# LiPoBattery.net
KiCad netlist of a schematic drawn in Altium Designer
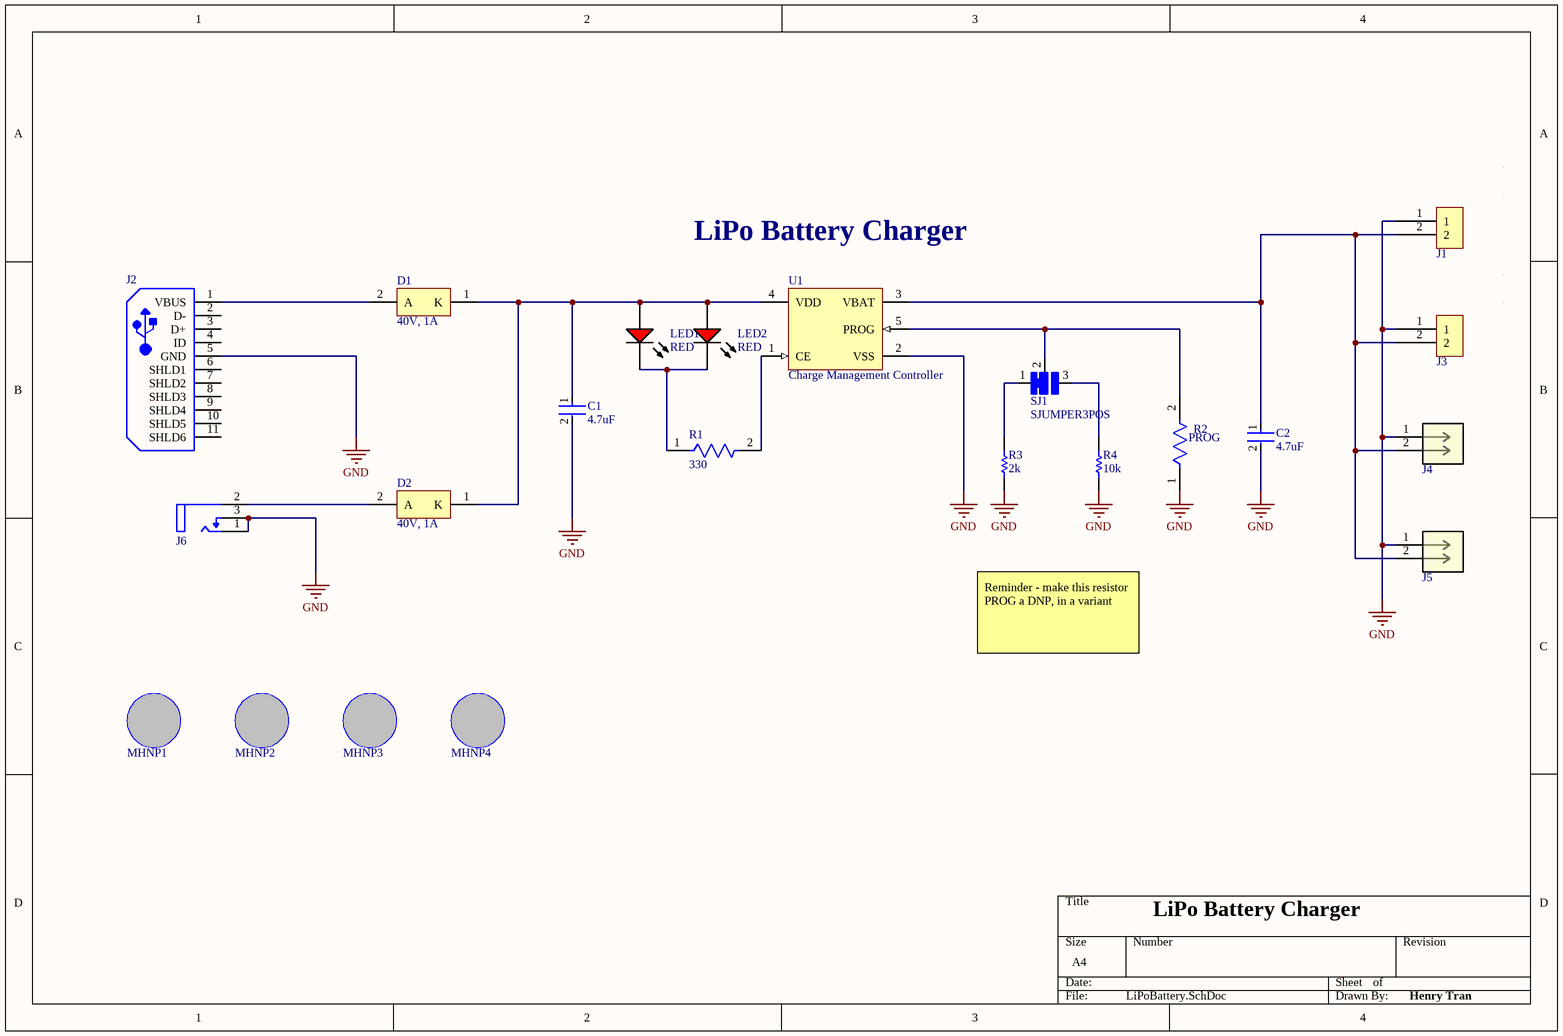
[diagram p0: LiPoBattery.SchDoc]

(export (version "E")
  (design (tool "Eeschema 10.0.6"))
  (components
    (comp (ref "C1")
      (value "4.7uF")
      (footprint "FP-CC0805-0_85-MFG")
      (description "CAP CER 4.7UF 6.3V X5R 0805")
      (fields (field (name "MANUFACTURER") "Yageo") (field (name "TOLERANCE") "0.1"))
      (libsource (lib "Altium Content Vault") (part "11868f565c42a9108669ba33697ecf6"))
    )
    (comp (ref "C2")
      (value "4.7uF")
      (footprint "FP-CC0805-0_85-MFG")
      (description "CAP CER 4.7UF 6.3V X5R 0805")
      (fields (field (name "MANUFACTURER") "Yageo") (field (name "TOLERANCE") "0.1"))
      (libsource (lib "Altium Content Vault") (part "11868f565c42a9108669ba33697ecf6"))
    )
    (comp (ref "D1")
      (value "40V, 1A")
      (footprint "ONSC-SMA-2-403D-02_V")
      (description "Schottky Power Rectifier, 2-Pin SMA, Pb-Free, Tape and Reel")
      (fields (field (name "PARTNUMBER") "MBRA140T3G") (field (name "MANUFACTURER") "On Semiconductor"))
      (libsource (lib "Altium Content Vault") (part "ONSC-D-K1A2-2_A"))
    )
    (comp (ref "D2")
      (value "40V, 1A")
      (footprint "ONSC-SMA-2-403D-02_V")
      (description "Schottky Power Rectifier, 2-Pin SMA, Pb-Free, Tape and Reel")
      (fields (field (name "PARTNUMBER") "MBRA140T3G") (field (name "MANUFACTURER") "On Semiconductor"))
      (libsource (lib "Altium Content Vault") (part "ONSC-D-K1A2-2_A"))
    )
    (comp (ref "J1")
      (value "CONN HEADER R/A 2POS 5.08MM")
      (footprint "1-179276-2")
      (description "Connector Header Through Hole, Right Angle 2 position 0.200\" (5.08mm)")
      (fields
        (field (name "MANUFACTURER") "TE Connectivity AMP Connectors")
        (field (name "MANUFACTURER PART NUMBER") "1-179276-2")
      )
      (libsource (lib "LiPoBattery") (part "1-179276-2"))
    )
    (comp (ref "J2")
      (value "105017-0001")
      (footprint "USB-MICRO-B_V")
      (fields (field (name "MANUFACTURER") "Molex"))
      (libsource (lib "Altium Content Vault") (part "USB-5-6SHLD"))
    )
    (comp (ref "J3")
      (value "CONN HEADER R/A 2POS 5.08MM")
      (footprint "1-179276-2")
      (description "Connector Header Through Hole, Right Angle 2 position 0.200\" (5.08mm)")
      (fields
        (field (name "MANUFACTURER") "TE Connectivity AMP Connectors")
        (field (name "MANUFACTURER PART NUMBER") "1-179276-2")
      )
      (libsource (lib "LiPoBattery") (part "1-179276-2"))
    )
    (comp (ref "J4")
      (value "2 POS VERT HEADER  0.100\"")
      (footprint "2Pins_AMP")
      (description "Connector Header Through Hole 2 position")
      (libsource (lib "LiPoBattery") (part "67997-402HLF"))
    )
    (comp (ref "J5")
      (value "2 POS VERT HEADER  0.100\"")
      (footprint "2Pins_AMP")
      (description "Connector Header Through Hole 2 position")
      (libsource (lib "LiPoBattery") (part "67997-402HLF"))
    )
    (comp (ref "J6")
      (value "CONN PWR JACK 2.1X5.5MM SOLDER")
      (footprint "FP-RASM722PTR13X-MFG")
      (libsource (lib "Altium Content Vault") (part "69023cd999ddc70d2a190894d9bbb58"))
    )
    (comp (ref "LED1")
      (value "RED")
      (footprint "VISH-TLMS1000_V")
      (description "Low Current LED, 40 mW, 1.8 V, -40 to 100 degC, 2-Pin SMD (0603), RoHS, Tape and Reel")
      (fields (field (name "MANUFACTURER") "Vishay"))
      (libsource (lib "Altium Content Vault") (part "LED-RED-AK-2"))
    )
    (comp (ref "LED2")
      (value "RED")
      (footprint "VISH-TLMS1000_V")
      (description "Low Current LED, 40 mW, 1.8 V, -40 to 100 degC, 2-Pin SMD (0603), RoHS, Tape and Reel")
      (fields (field (name "MANUFACTURER") "Vishay"))
      (libsource (lib "Altium Content Vault") (part "LED-RED-AK-2"))
    )
    (comp (ref "MHNP1")
      (value "Mounting Hole Non-Plated 3.2mm")
      (footprint "MTHNP3P2MM")
      (description "Mounting Hole Non-Plated 3.2mm drill hole")
      (libsource (lib "LiPoBattery") (part "MTHNP3P2MM"))
    )
    (comp (ref "MHNP2")
      (value "Mounting Hole Non-Plated 3.2mm")
      (footprint "MTHNP3P2MM")
      (description "Mounting Hole Non-Plated 3.2mm drill hole")
      (libsource (lib "LiPoBattery") (part "MTHNP3P2MM"))
    )
    (comp (ref "MHNP3")
      (value "Mounting Hole Non-Plated 3.2mm")
      (footprint "MTHNP3P2MM")
      (description "Mounting Hole Non-Plated 3.2mm drill hole")
      (libsource (lib "LiPoBattery") (part "MTHNP3P2MM"))
    )
    (comp (ref "MHNP4")
      (value "Mounting Hole Non-Plated 3.2mm")
      (footprint "MTHNP3P2MM")
      (description "Mounting Hole Non-Plated 3.2mm drill hole")
      (libsource (lib "LiPoBattery") (part "MTHNP3P2MM"))
    )
    (comp (ref "R1")
      (value "330")
      (footprint "FP-CRCW0805-e3-MFG")
      (description "RES Thick Film, 330Ω, 1%, 0.125W, 100ppm/°C, 0805")
      (fields (field (name "TOLERANCE") "1%"))
      (libsource (lib "Altium Content Vault") (part "1029c3af85768c4190bb7ad29bc67b5"))
    )
    (comp (ref "R2")
      (value "PROG")
      (footprint "FP-MRS25-MFG")
      (fields (field (name "TOLERANCE") "1%"))
      (libsource (lib "Altium Content Vault") (part "1029c3af85768c4190bb7ad29bc67b5"))
    )
    (comp (ref "R3")
      (value "2k")
      (footprint "RESC2013X70X40ML20T20")
      (fields (field (name "PART NUMBER") "ERJ-6GEYJ202V") (field (name "MANUFACTURER") "Panasonic"))
      (libsource (lib "Altium Content Vault") (part "RES"))
    )
    (comp (ref "R4")
      (value "10k")
      (footprint "RESC2013X70X40ML20T20")
      (fields (field (name "MANUFACTURER") "Panasonic") (field (name "PART NUMBER") "ERJ-6ENF1002V"))
      (libsource (lib "Altium Content Vault") (part "RES"))
    )
    (comp (ref "SJ1")
      (value "SJUMPER3POS")
      (footprint "SJUMPER3POS-Footprint-1")
      (description "Solder jumer 3 pads and pins")
      (libsource (lib "Altium 365 Cloud") (part "SJUMPER3POS-Symbol-1"))
    )
    (comp (ref "U1")
      (value "Charge Management Controller")
      (footprint "SOT-23-OT5_M")
      (libsource (lib "Altium Content Vault") (part "PM-BM-MCP7381X-SOT5"))
    )
  )
  (nets
    (net (code "1") (name "GND") (class "Default")
      (node (ref "C1") (pin "2") (pinfunction "2_2") (pintype "passive"))
      (node (ref "C2") (pin "2") (pinfunction "2_2") (pintype "passive"))
      (node (ref "J1") (pin "1") (pinfunction "1_1") (pintype "passive"))
      (node (ref "J2") (pin "5") (pinfunction "GND_5") (pintype "passive"))
      (node (ref "J3") (pin "1") (pinfunction "1_1") (pintype "passive"))
      (node (ref "J4") (pin "1") (pinfunction "1_1") (pintype "passive"))
      (node (ref "J5") (pin "1") (pinfunction "1_1") (pintype "passive"))
      (node (ref "J6") (pin "1") (pinfunction "TIP_TERMINAL(CENTER_PIN)_1") (pintype "passive"))
      (node (ref "J6") (pin "3") (pinfunction "SHUNT_TERMINAL_3") (pintype "passive"))
      (node (ref "R2") (pin "1") (pinfunction "1_1") (pintype "passive"))
      (node (ref "R3") (pin "1") (pinfunction "1_1") (pintype "passive"))
      (node (ref "R4") (pin "1") (pinfunction "1_1") (pintype "passive"))
      (node (ref "U1") (pin "2") (pinfunction "VSS_2") (pintype "power_in"))
    )
    (net (code "2") (name "Net-(D1-A)") (class "Default")
      (node (ref "D1") (pin "2") (pinfunction "A_2") (pintype "passive"))
      (node (ref "J2") (pin "1") (pinfunction "VBUS_1") (pintype "passive"))
    )
    (net (code "3") (name "Net-(D1-K)") (class "Default")
      (node (ref "C1") (pin "1") (pinfunction "1_1") (pintype "passive"))
      (node (ref "D1") (pin "1") (pinfunction "K_1") (pintype "passive"))
      (node (ref "D2") (pin "1") (pinfunction "K_1") (pintype "passive"))
      (node (ref "LED1") (pin "1") (pinfunction "A_1") (pintype "passive"))
      (node (ref "LED2") (pin "1") (pinfunction "A_1") (pintype "passive"))
      (node (ref "U1") (pin "4") (pinfunction "VDD_4") (pintype "power_in"))
    )
    (net (code "4") (name "Net-(D2-A)") (class "Default")
      (node (ref "D2") (pin "2") (pinfunction "A_2") (pintype "passive"))
      (node (ref "J6") (pin "2") (pinfunction "SLEEVE_TERMINAL_2") (pintype "passive"))
    )
    (net (code "5") (name "Net-(LED1-K)") (class "Default")
      (node (ref "LED1") (pin "2") (pinfunction "K_2") (pintype "passive"))
      (node (ref "LED2") (pin "2") (pinfunction "K_2") (pintype "passive"))
      (node (ref "R1") (pin "1") (pinfunction "1_1") (pintype "passive"))
    )
    (net (code "6") (name "Net-(R3-Pad2)") (class "Default")
      (node (ref "R3") (pin "2") (pinfunction "2_2") (pintype "passive"))
      (node (ref "SJ1") (pin "1") (pinfunction "1_1") (pintype "passive"))
    )
    (net (code "7") (name "Net-(R4-Pad2)") (class "Default")
      (node (ref "R4") (pin "2") (pinfunction "2_2") (pintype "passive"))
      (node (ref "SJ1") (pin "3") (pinfunction "3_3") (pintype "passive"))
    )
    (net (code "8") (name "Net-(U1-CE)") (class "Default")
      (node (ref "R1") (pin "2") (pinfunction "2_2") (pintype "passive"))
      (node (ref "U1") (pin "1") (pinfunction "CE_1") (pintype "input"))
    )
    (net (code "9") (name "Net-(U1-PROG)") (class "Default")
      (node (ref "R2") (pin "2") (pinfunction "2_2") (pintype "passive"))
      (node (ref "SJ1") (pin "2") (pinfunction "2_2") (pintype "passive"))
      (node (ref "U1") (pin "5") (pinfunction "PROG_5") (pintype "input"))
    )
    (net (code "10") (name "Net-(U1-VBAT)") (class "Default")
      (node (ref "C2") (pin "1") (pinfunction "1_1") (pintype "passive"))
      (node (ref "J1") (pin "2") (pinfunction "2_2") (pintype "passive"))
      (node (ref "J3") (pin "2") (pinfunction "2_2") (pintype "passive"))
      (node (ref "J4") (pin "2") (pinfunction "2_2") (pintype "passive"))
      (node (ref "J5") (pin "2") (pinfunction "2_2") (pintype "passive"))
      (node (ref "U1") (pin "3") (pinfunction "VBAT_3") (pintype "power_in"))
    )
    (net (code "11") (name "unconnected-(J2-D+-Pad3)") (class "Default")
      (node (ref "J2") (pin "3") (pinfunction "D+_3") (pintype "passive"))
    )
    (net (code "12") (name "unconnected-(J2-D--Pad2)") (class "Default")
      (node (ref "J2") (pin "2") (pinfunction "D-_2") (pintype "passive"))
    )
    (net (code "13") (name "unconnected-(J2-ID-Pad4)") (class "Default")
      (node (ref "J2") (pin "4") (pinfunction "ID_4") (pintype "passive"))
    )
    (net (code "14") (name "unconnected-(J2-SHLD1-Pad6)") (class "Default")
      (node (ref "J2") (pin "6") (pinfunction "SHLD1_6") (pintype "passive"))
    )
    (net (code "15") (name "unconnected-(J2-SHLD2-Pad7)") (class "Default")
      (node (ref "J2") (pin "7") (pinfunction "SHLD2_7") (pintype "passive"))
    )
    (net (code "16") (name "unconnected-(J2-SHLD3-Pad8)") (class "Default")
      (node (ref "J2") (pin "8") (pinfunction "SHLD3_8") (pintype "passive"))
    )
    (net (code "17") (name "unconnected-(J2-SHLD4-Pad9)") (class "Default")
      (node (ref "J2") (pin "9") (pinfunction "SHLD4_9") (pintype "passive"))
    )
    (net (code "18") (name "unconnected-(J2-SHLD5-Pad10)") (class "Default")
      (node (ref "J2") (pin "10") (pinfunction "SHLD5_10") (pintype "passive"))
    )
    (net (code "19") (name "unconnected-(J2-SHLD6-Pad11)") (class "Default")
      (node (ref "J2") (pin "11") (pinfunction "SHLD6_11") (pintype "passive"))
    )
  )
)
